# ADC-RDC-Power.net
KiCad netlist of a schematic drawn in Altium Designer
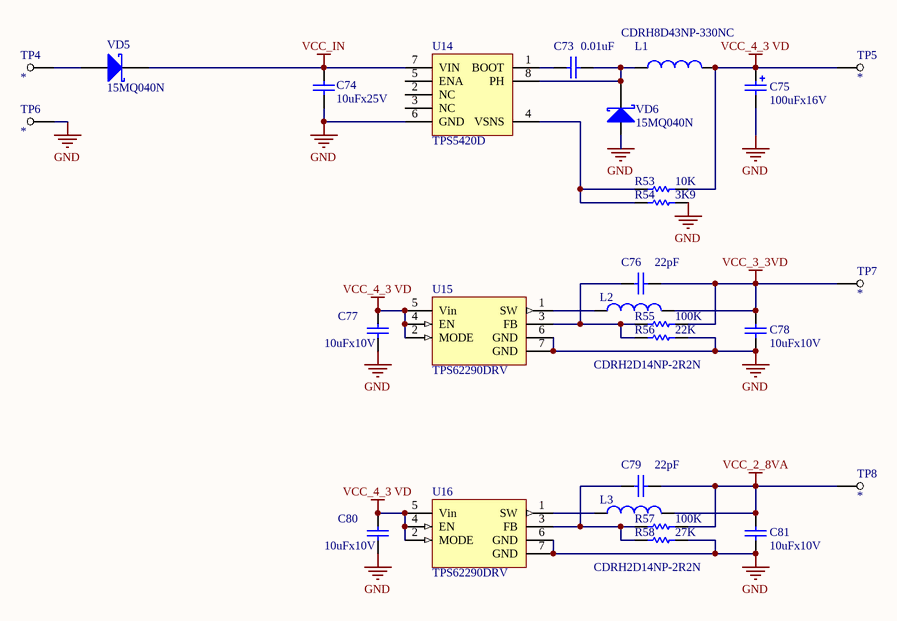
[diagram p0: ADC-RDC-Power.SchDoc]

(export (version "E")
  (design (tool "Eeschema 10.0.6"))
  (components
    (comp (ref "C73")
      (value "0.01uF")
      (footprint "C0603")
      (description "Capacitor, 2pin")
      (libsource (lib "GC500EM2") (part "Cap"))
    )
    (comp (ref "C74")
      (value "10uFx25V")
      (footprint "C1210")
      (description "Capacitor, 2pin")
      (libsource (lib "GC500EM2") (part "Cap"))
    )
    (comp (ref "C75")
      (value "100uFx16V")
      (footprint "SIZE E")
      (description "Polarized Capacitor, 2pin")
      (libsource (lib "GC500EM2") (part "Cap Pol"))
    )
    (comp (ref "C76")
      (value "22pF")
      (footprint "C0603")
      (description "Capacitor, 2pin")
      (libsource (lib "GC500EM2") (part "Cap"))
    )
    (comp (ref "C77")
      (value "10uFx10V")
      (footprint "C0805")
      (description "Capacitor, 2pin")
      (libsource (lib "GC500EM2") (part "Cap"))
    )
    (comp (ref "C78")
      (value "10uFx10V")
      (footprint "C0805")
      (description "Capacitor, 2pin")
      (libsource (lib "GC500EM2") (part "Cap"))
    )
    (comp (ref "C79")
      (value "22pF")
      (footprint "C0603")
      (description "Capacitor, 2pin")
      (libsource (lib "GC500EM2") (part "Cap"))
    )
    (comp (ref "C80")
      (value "10uFx10V")
      (footprint "C0805")
      (description "Capacitor, 2pin")
      (libsource (lib "GC500EM2") (part "Cap"))
    )
    (comp (ref "C81")
      (value "10uFx10V")
      (footprint "C0805")
      (description "Capacitor, 2pin")
      (libsource (lib "GC500EM2") (part "Cap"))
    )
    (comp (ref "L1")
      (value "CDRH8D43NP-330NC")
      (footprint "CDRH8D43")
      (description "Inductor, 2pin")
      (libsource (lib "GC500EM2") (part "Inductor"))
    )
    (comp (ref "L2")
      (value "CDRH2D14NP-2R2N")
      (footprint "CDRH2D18")
      (description "Inductor, 2pin")
      (libsource (lib "GC500EM2") (part "Inductor"))
    )
    (comp (ref "L3")
      (value "CDRH2D14NP-2R2N")
      (footprint "CDRH2D18")
      (description "Inductor, 2pin")
      (libsource (lib "GC500EM2") (part "Inductor"))
    )
    (comp (ref "R53")
      (value "10K")
      (footprint "R0603")
      (description "Resistor, 2pin")
      (libsource (lib "GC500EM2") (part "RES"))
    )
    (comp (ref "R54")
      (value "3K9")
      (footprint "R0603")
      (description "Resistor, 2pin")
      (libsource (lib "GC500EM2") (part "RES"))
    )
    (comp (ref "R55")
      (value "100K")
      (footprint "R0603")
      (description "Resistor, 2pin")
      (libsource (lib "GC500EM2") (part "RES"))
    )
    (comp (ref "R56")
      (value "22K")
      (footprint "R0603")
      (description "Resistor, 2pin")
      (libsource (lib "GC500EM2") (part "RES"))
    )
    (comp (ref "R57")
      (value "100K")
      (footprint "R0603")
      (description "Resistor, 2pin")
      (libsource (lib "GC500EM2") (part "RES"))
    )
    (comp (ref "R58")
      (value "27K")
      (footprint "R0603")
      (description "Resistor, 2pin")
      (libsource (lib "GC500EM2") (part "RES"))
    )
    (comp (ref "TP4")
      (value "*")
      (footprint "TP_18_10")
      (description "Test point")
      (libsource (lib "GC500EM2") (part "Test_point"))
    )
    (comp (ref "TP5")
      (value "*")
      (footprint "TP_1_06")
      (description "Test point")
      (libsource (lib "GC500EM2") (part "Test_point"))
    )
    (comp (ref "TP6")
      (value "*")
      (footprint "TP_18_10")
      (description "Test point")
      (libsource (lib "GC500EM2") (part "Test_point"))
    )
    (comp (ref "TP7")
      (value "*")
      (footprint "TP_1_06")
      (description "Test point")
      (libsource (lib "GC500EM2") (part "Test_point"))
    )
    (comp (ref "TP8")
      (value "*")
      (footprint "TP_1_06")
      (description "Test point")
      (libsource (lib "GC500EM2") (part "Test_point"))
    )
    (comp (ref "U14")
      (value "TPS5420D")
      (footprint "SOIC8")
      (description "2-A, WIDE INPUT RANGE, STEP-DOWN SWIFT™ CONVERTER")
      (libsource (lib "GC500EM2") (part "TPS5420"))
    )
    (comp (ref "U15")
      (value "TPS62290DRV")
      (footprint "SON6")
      (description "1-A Step Down Converter in 2 x 2 SON Package")
      (libsource (lib "GC500EM2") (part "TPS62290"))
    )
    (comp (ref "U16")
      (value "TPS62290DRV")
      (footprint "SON6")
      (description "1-A Step Down Converter in 2 x 2 SON Package")
      (libsource (lib "GC500EM2") (part "TPS62290"))
    )
    (comp (ref "VD5")
      (value "15MQ040N")
      (footprint "SMA")
      (description "Schottky Diode, 2pin")
      (libsource (lib "GC500EM2") (part "D Schottky"))
    )
    (comp (ref "VD6")
      (value "15MQ040N")
      (footprint "SMA")
      (description "Schottky Diode, 2pin")
      (libsource (lib "GC500EM2") (part "D Schottky"))
    )
  )
  (nets
    (net (code "1") (name "GND") (class "Default")
      (node (ref "C74") (pin "2") (pinfunction "2_2") (pintype "passive"))
      (node (ref "C75") (pin "2") (pinfunction "2_2") (pintype "passive"))
      (node (ref "C77") (pin "2") (pinfunction "2_2") (pintype "passive"))
      (node (ref "C78") (pin "2") (pinfunction "2_2") (pintype "passive"))
      (node (ref "C80") (pin "2") (pinfunction "2_2") (pintype "passive"))
      (node (ref "C81") (pin "2") (pinfunction "2_2") (pintype "passive"))
      (node (ref "R54") (pin "2") (pinfunction "2_2") (pintype "passive"))
      (node (ref "R56") (pin "2") (pinfunction "2_2") (pintype "passive"))
      (node (ref "R58") (pin "2") (pinfunction "2_2") (pintype "passive"))
      (node (ref "TP6") (pin "1") (pinfunction "1_1") (pintype "passive"))
      (node (ref "U14") (pin "6") (pinfunction "GND_6") (pintype "passive"))
      (node (ref "U15") (pin "6") (pinfunction "GND_6") (pintype "passive"))
      (node (ref "U15") (pin "7") (pinfunction "GND_7") (pintype "passive"))
      (node (ref "U16") (pin "6") (pinfunction "GND_6") (pintype "passive"))
      (node (ref "U16") (pin "7") (pinfunction "GND_7") (pintype "passive"))
      (node (ref "VD6") (pin "1") (pinfunction "A_1") (pintype "passive"))
    )
    (net (code "2") (name "Net-(U14-BOOT)") (class "Default")
      (node (ref "C73") (pin "1") (pinfunction "1_1") (pintype "passive"))
      (node (ref "U14") (pin "1") (pinfunction "BOOT_1") (pintype "passive"))
    )
    (net (code "3") (name "Net-(U14-PH)") (class "Default")
      (node (ref "C73") (pin "2") (pinfunction "2_2") (pintype "passive"))
      (node (ref "L1") (pin "1") (pinfunction "1_1") (pintype "passive"))
      (node (ref "U14") (pin "8") (pinfunction "PH_8") (pintype "passive"))
      (node (ref "VD6") (pin "2") (pinfunction "K_2") (pintype "passive"))
    )
    (net (code "4") (name "Net-(U14-VSNS)") (class "Default")
      (node (ref "R53") (pin "1") (pinfunction "1_1") (pintype "passive"))
      (node (ref "R54") (pin "1") (pinfunction "1_1") (pintype "passive"))
      (node (ref "U14") (pin "4") (pinfunction "VSNS_4") (pintype "passive"))
    )
    (net (code "5") (name "Net-(U15-FB)") (class "Default")
      (node (ref "C76") (pin "2") (pinfunction "2_2") (pintype "passive"))
      (node (ref "R55") (pin "1") (pinfunction "1_1") (pintype "passive"))
      (node (ref "R56") (pin "1") (pinfunction "1_1") (pintype "passive"))
      (node (ref "U15") (pin "3") (pinfunction "FB_3") (pintype "passive"))
    )
    (net (code "6") (name "Net-(U15-SW)") (class "Default")
      (node (ref "L2") (pin "1") (pinfunction "1_1") (pintype "passive"))
      (node (ref "U15") (pin "1") (pinfunction "SW_1") (pintype "output"))
    )
    (net (code "7") (name "Net-(U16-FB)") (class "Default")
      (node (ref "C79") (pin "2") (pinfunction "2_2") (pintype "passive"))
      (node (ref "R57") (pin "1") (pinfunction "1_1") (pintype "passive"))
      (node (ref "R58") (pin "1") (pinfunction "1_1") (pintype "passive"))
      (node (ref "U16") (pin "3") (pinfunction "FB_3") (pintype "passive"))
    )
    (net (code "8") (name "Net-(U16-SW)") (class "Default")
      (node (ref "L3") (pin "1") (pinfunction "1_1") (pintype "passive"))
      (node (ref "U16") (pin "1") (pinfunction "SW_1") (pintype "output"))
    )
    (net (code "9") (name "Net-(VD5-A)") (class "Default")
      (node (ref "TP4") (pin "1") (pinfunction "1_1") (pintype "passive"))
      (node (ref "VD5") (pin "1") (pinfunction "A_1") (pintype "passive"))
    )
    (net (code "10") (name "VCC_2_8VA") (class "Default")
      (node (ref "C79") (pin "1") (pinfunction "1_1") (pintype "passive"))
      (node (ref "C81") (pin "1") (pinfunction "1_1") (pintype "passive"))
      (node (ref "L3") (pin "2") (pinfunction "2_2") (pintype "passive"))
      (node (ref "R57") (pin "2") (pinfunction "2_2") (pintype "passive"))
      (node (ref "TP8") (pin "1") (pinfunction "1_1") (pintype "passive"))
    )
    (net (code "11") (name "VCC_3_3VD") (class "Default")
      (node (ref "C76") (pin "1") (pinfunction "1_1") (pintype "passive"))
      (node (ref "C78") (pin "1") (pinfunction "1_1") (pintype "passive"))
      (node (ref "L2") (pin "2") (pinfunction "2_2") (pintype "passive"))
      (node (ref "R55") (pin "2") (pinfunction "2_2") (pintype "passive"))
      (node (ref "TP7") (pin "1") (pinfunction "1_1") (pintype "passive"))
    )
    (net (code "12") (name "VCC_4_3 VD") (class "Default")
      (node (ref "C75") (pin "1") (pinfunction "1_1") (pintype "passive"))
      (node (ref "C77") (pin "1") (pinfunction "1_1") (pintype "passive"))
      (node (ref "C80") (pin "1") (pinfunction "1_1") (pintype "passive"))
      (node (ref "L1") (pin "2") (pinfunction "2_2") (pintype "passive"))
      (node (ref "R53") (pin "2") (pinfunction "2_2") (pintype "passive"))
      (node (ref "TP5") (pin "1") (pinfunction "1_1") (pintype "passive"))
      (node (ref "U15") (pin "2") (pinfunction "MODE_2") (pintype "input"))
      (node (ref "U15") (pin "4") (pinfunction "EN_4") (pintype "input"))
      (node (ref "U15") (pin "5") (pinfunction "Vin_5") (pintype "passive"))
      (node (ref "U16") (pin "2") (pinfunction "MODE_2") (pintype "input"))
      (node (ref "U16") (pin "4") (pinfunction "EN_4") (pintype "input"))
      (node (ref "U16") (pin "5") (pinfunction "Vin_5") (pintype "passive"))
    )
    (net (code "13") (name "VCC_IN") (class "Default")
      (node (ref "C74") (pin "1") (pinfunction "1_1") (pintype "passive"))
      (node (ref "U14") (pin "7") (pinfunction "VIN_7") (pintype "passive"))
      (node (ref "VD5") (pin "2") (pinfunction "K_2") (pintype "passive"))
    )
    (net (code "14") (name "unconnected-(U14-ENA-Pad5)") (class "Default")
      (node (ref "U14") (pin "5") (pinfunction "ENA_5") (pintype "passive"))
    )
    (net (code "15") (name "unconnected-(U14-NC-Pad2)") (class "Default")
      (node (ref "U14") (pin "2") (pinfunction "NC_2") (pintype "passive"))
    )
    (net (code "16") (name "unconnected-(U14-NC-Pad3)") (class "Default")
      (node (ref "U14") (pin "3") (pinfunction "NC_3") (pintype "passive"))
    )
  )
)
